# RHD2132-Millmax-RightAngle.net
KiCad netlist of a schematic drawn in EAGLE
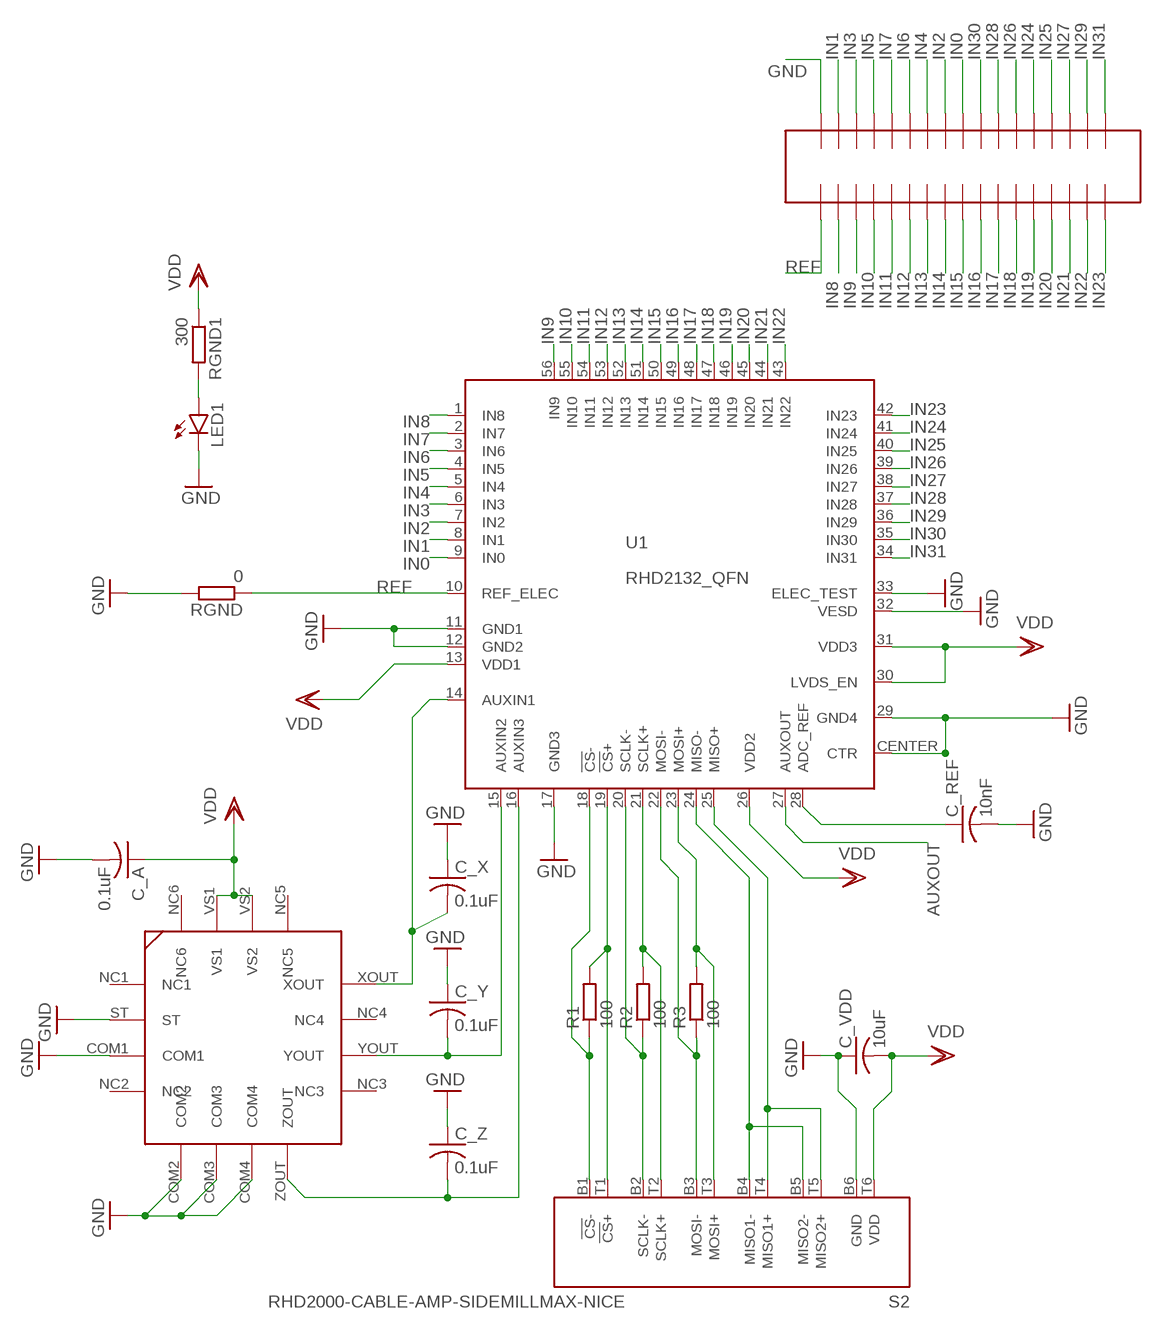
[diagram p0: schematic, sheet 1]

(export (version "E")
  (design (tool "Eeschema 10.0.6"))
  (components
    (comp (ref "C_A")
      (value "0.1uF")
      (footprint "eagle-import:C0402K")
      (libsource (lib "eagle-import") (part "C-USC0402K"))
    )
    (comp (ref "C_REF")
      (value "10nF")
      (footprint "eagle-import:C0402K")
      (libsource (lib "eagle-import") (part "C-USC0402K"))
    )
    (comp (ref "C_VDD")
      (value "10uF")
      (footprint "eagle-import:C1206")
      (libsource (lib "eagle-import") (part "C-USC1206"))
    )
    (comp (ref "C_X")
      (value "0.1uF")
      (footprint "eagle-import:C0402K")
      (libsource (lib "eagle-import") (part "C-USC0402K"))
    )
    (comp (ref "C_Y")
      (value "0.1uF")
      (footprint "eagle-import:C0402K")
      (libsource (lib "eagle-import") (part "C-USC0402K"))
    )
    (comp (ref "C_Z")
      (value "0.1uF")
      (footprint "eagle-import:C0402K")
      (libsource (lib "eagle-import") (part "C-USC0402K"))
    )
    (comp (ref "LED1")
      (value "LEDCHIPLED_0805")
      (footprint "eagle-import:CHIPLED_0805")
      (libsource (lib "eagle-import") (part "LEDCHIPLED_0805"))
    )
    (comp (ref "R1")
      (value "100")
      (footprint "eagle-import:R0402")
      (libsource (lib "eagle-import") (part "R-EU_R0402"))
    )
    (comp (ref "R2")
      (value "100")
      (footprint "eagle-import:R0402")
      (libsource (lib "eagle-import") (part "R-EU_R0402"))
    )
    (comp (ref "R3")
      (value "100")
      (footprint "eagle-import:R0402")
      (libsource (lib "eagle-import") (part "R-EU_R0402"))
    )
    (comp (ref "RGND")
      (value "0")
      (footprint "eagle-import:R0402")
      (libsource (lib "eagle-import") (part "R-EU_R0402"))
    )
    (comp (ref "RGND1")
      (value "300")
      (footprint "eagle-import:R0402")
      (libsource (lib "eagle-import") (part "R-EU_R0402"))
    )
    (comp (ref "S2")
      (value "RHD2000-CABLE-AMP-SIDEMILLMAX-NICE")
      (footprint "eagle-import:MILLMAX-12PIN-NICE")
      (libsource (lib "eagle-import") (part "RHD2000-CABLE-AMP-SIDEMILLMAX-NICE"))
    )
    (comp (ref "U$1")
      (value "ADXL335")
      (footprint "eagle-import:ADXL335")
      (libsource (lib "eagle-import") (part "ADXL335"))
    )
    (comp (ref "U$2")
      (value "FTSH-117BOARD-END")
      (footprint "eagle-import:FTSH-117-END")
      (libsource (lib "eagle-import") (part "FTSH-117BOARD-END"))
    )
    (comp (ref "U1")
      (value "RHD2132_QFN")
      (footprint "eagle-import:QFN56_8_X_8_LARGE")
      (libsource (lib "eagle-import") (part "RHD2132_QFN"))
    )
  )
  (nets
    (net (code "1") (name "/AUXOUT") (class "Default")
      (node (ref "U1") (pin "27") (pinfunction "AUXOUT_27") (pintype "tri_state"))
    )
    (net (code "2") (name "/IN0") (class "Default")
      (node (ref "U$2") (pin "P$26") (pinfunction "P$26_P$26") (pintype "bidirectional"))
      (node (ref "U1") (pin "9") (pinfunction "IN0_9") (pintype "input"))
    )
    (net (code "3") (name "/IN1") (class "Default")
      (node (ref "U$2") (pin "P$33") (pinfunction "P$33_P$33") (pintype "bidirectional"))
      (node (ref "U1") (pin "8") (pinfunction "IN1_8") (pintype "input"))
    )
    (net (code "4") (name "/IN2") (class "Default")
      (node (ref "U$2") (pin "P$27") (pinfunction "P$27_P$27") (pintype "bidirectional"))
      (node (ref "U1") (pin "7") (pinfunction "IN2_7") (pintype "input"))
    )
    (net (code "5") (name "/IN3") (class "Default")
      (node (ref "U$2") (pin "P$32") (pinfunction "P$32_P$32") (pintype "bidirectional"))
      (node (ref "U1") (pin "6") (pinfunction "IN3_6") (pintype "input"))
    )
    (net (code "6") (name "/IN4") (class "Default")
      (node (ref "U$2") (pin "P$28") (pinfunction "P$28_P$28") (pintype "bidirectional"))
      (node (ref "U1") (pin "5") (pinfunction "IN4_5") (pintype "input"))
    )
    (net (code "7") (name "/IN5") (class "Default")
      (node (ref "U$2") (pin "P$31") (pinfunction "P$31_P$31") (pintype "bidirectional"))
      (node (ref "U1") (pin "4") (pinfunction "IN5_4") (pintype "input"))
    )
    (net (code "8") (name "/IN6") (class "Default")
      (node (ref "U$2") (pin "P$29") (pinfunction "P$29_P$29") (pintype "bidirectional"))
      (node (ref "U1") (pin "3") (pinfunction "IN6_3") (pintype "input"))
    )
    (net (code "9") (name "/IN7") (class "Default")
      (node (ref "U$2") (pin "P$30") (pinfunction "P$30_P$30") (pintype "bidirectional"))
      (node (ref "U1") (pin "2") (pinfunction "IN7_2") (pintype "input"))
    )
    (net (code "10") (name "/IN8") (class "Default")
      (node (ref "U$2") (pin "P$2") (pinfunction "P$2_P$2") (pintype "bidirectional"))
      (node (ref "U1") (pin "1") (pinfunction "IN8_1") (pintype "input"))
    )
    (net (code "11") (name "/IN9") (class "Default")
      (node (ref "U$2") (pin "P$3") (pinfunction "P$3_P$3") (pintype "bidirectional"))
      (node (ref "U1") (pin "56") (pinfunction "IN9_56") (pintype "input"))
    )
    (net (code "12") (name "/IN10") (class "Default")
      (node (ref "U$2") (pin "P$4") (pinfunction "P$4_P$4") (pintype "bidirectional"))
      (node (ref "U1") (pin "55") (pinfunction "IN10_55") (pintype "input"))
    )
    (net (code "13") (name "/IN11") (class "Default")
      (node (ref "U$2") (pin "P$5") (pinfunction "P$5_P$5") (pintype "bidirectional"))
      (node (ref "U1") (pin "54") (pinfunction "IN11_54") (pintype "input"))
    )
    (net (code "14") (name "/IN12") (class "Default")
      (node (ref "U$2") (pin "P$6") (pinfunction "P$6_P$6") (pintype "bidirectional"))
      (node (ref "U1") (pin "53") (pinfunction "IN12_53") (pintype "input"))
    )
    (net (code "15") (name "/IN13") (class "Default")
      (node (ref "U$2") (pin "P$7") (pinfunction "P$7_P$7") (pintype "bidirectional"))
      (node (ref "U1") (pin "52") (pinfunction "IN13_52") (pintype "input"))
    )
    (net (code "16") (name "/IN14") (class "Default")
      (node (ref "U$2") (pin "P$8") (pinfunction "P$8_P$8") (pintype "bidirectional"))
      (node (ref "U1") (pin "51") (pinfunction "IN14_51") (pintype "input"))
    )
    (net (code "17") (name "/IN15") (class "Default")
      (node (ref "U$2") (pin "P$9") (pinfunction "P$9_P$9") (pintype "bidirectional"))
      (node (ref "U1") (pin "50") (pinfunction "IN15_50") (pintype "input"))
    )
    (net (code "18") (name "/IN16") (class "Default")
      (node (ref "U$2") (pin "P$10") (pinfunction "P$10_P$10") (pintype "bidirectional"))
      (node (ref "U1") (pin "49") (pinfunction "IN16_49") (pintype "input"))
    )
    (net (code "19") (name "/IN17") (class "Default")
      (node (ref "U$2") (pin "P$11") (pinfunction "P$11_P$11") (pintype "bidirectional"))
      (node (ref "U1") (pin "48") (pinfunction "IN17_48") (pintype "input"))
    )
    (net (code "20") (name "/IN18") (class "Default")
      (node (ref "U$2") (pin "P$12") (pinfunction "P$12_P$12") (pintype "bidirectional"))
      (node (ref "U1") (pin "47") (pinfunction "IN18_47") (pintype "input"))
    )
    (net (code "21") (name "/IN19") (class "Default")
      (node (ref "U$2") (pin "P$13") (pinfunction "P$13_P$13") (pintype "bidirectional"))
      (node (ref "U1") (pin "46") (pinfunction "IN19_46") (pintype "input"))
    )
    (net (code "22") (name "/IN20") (class "Default")
      (node (ref "U$2") (pin "P$14") (pinfunction "P$14_P$14") (pintype "bidirectional"))
      (node (ref "U1") (pin "45") (pinfunction "IN20_45") (pintype "input"))
    )
    (net (code "23") (name "/IN21") (class "Default")
      (node (ref "U$2") (pin "P$15") (pinfunction "P$15_P$15") (pintype "bidirectional"))
      (node (ref "U1") (pin "44") (pinfunction "IN21_44") (pintype "input"))
    )
    (net (code "24") (name "/IN22") (class "Default")
      (node (ref "U$2") (pin "P$16") (pinfunction "P$16_P$16") (pintype "bidirectional"))
      (node (ref "U1") (pin "43") (pinfunction "IN22_43") (pintype "input"))
    )
    (net (code "25") (name "/IN23") (class "Default")
      (node (ref "U$2") (pin "P$17") (pinfunction "P$17_P$17") (pintype "bidirectional"))
      (node (ref "U1") (pin "42") (pinfunction "IN23_42") (pintype "input"))
    )
    (net (code "26") (name "/IN24") (class "Default")
      (node (ref "U$2") (pin "P$22") (pinfunction "P$22_P$22") (pintype "bidirectional"))
      (node (ref "U1") (pin "41") (pinfunction "IN24_41") (pintype "input"))
    )
    (net (code "27") (name "/IN25") (class "Default")
      (node (ref "U$2") (pin "P$21") (pinfunction "P$21_P$21") (pintype "bidirectional"))
      (node (ref "U1") (pin "40") (pinfunction "IN25_40") (pintype "input"))
    )
    (net (code "28") (name "/IN26") (class "Default")
      (node (ref "U$2") (pin "P$23") (pinfunction "P$23_P$23") (pintype "bidirectional"))
      (node (ref "U1") (pin "39") (pinfunction "IN26_39") (pintype "input"))
    )
    (net (code "29") (name "/IN27") (class "Default")
      (node (ref "U$2") (pin "P$20") (pinfunction "P$20_P$20") (pintype "bidirectional"))
      (node (ref "U1") (pin "38") (pinfunction "IN27_38") (pintype "input"))
    )
    (net (code "30") (name "/IN28") (class "Default")
      (node (ref "U$2") (pin "P$24") (pinfunction "P$24_P$24") (pintype "bidirectional"))
      (node (ref "U1") (pin "37") (pinfunction "IN28_37") (pintype "input"))
    )
    (net (code "31") (name "/IN29") (class "Default")
      (node (ref "U$2") (pin "P$19") (pinfunction "P$19_P$19") (pintype "bidirectional"))
      (node (ref "U1") (pin "36") (pinfunction "IN29_36") (pintype "input"))
    )
    (net (code "32") (name "/IN30") (class "Default")
      (node (ref "U$2") (pin "P$25") (pinfunction "P$25_P$25") (pintype "bidirectional"))
      (node (ref "U1") (pin "35") (pinfunction "IN30_35") (pintype "input"))
    )
    (net (code "33") (name "/IN31") (class "Default")
      (node (ref "U$2") (pin "P$18") (pinfunction "P$18_P$18") (pintype "bidirectional"))
      (node (ref "U1") (pin "34") (pinfunction "IN31_34") (pintype "input"))
    )
    (net (code "34") (name "/REF") (class "Default")
      (node (ref "RGND") (pin "1") (pinfunction "1_1") (pintype "passive"))
      (node (ref "U$2") (pin "P$1") (pinfunction "P$1_P$1") (pintype "bidirectional"))
      (node (ref "U1") (pin "10") (pinfunction "REF_ELEC_10") (pintype "input"))
    )
    (net (code "35") (name "GND") (class "Default")
      (node (ref "C_A") (pin "2") (pinfunction "2_2") (pintype "passive"))
      (node (ref "C_REF") (pin "2") (pinfunction "2_2") (pintype "passive"))
      (node (ref "C_VDD") (pin "1") (pinfunction "1_1") (pintype "passive"))
      (node (ref "C_X") (pin "1") (pinfunction "1_1") (pintype "passive"))
      (node (ref "C_Y") (pin "1") (pinfunction "1_1") (pintype "passive"))
      (node (ref "C_Z") (pin "1") (pinfunction "1_1") (pintype "passive"))
      (node (ref "LED1") (pin "C") (pinfunction "C_C") (pintype "passive"))
      (node (ref "RGND") (pin "2") (pinfunction "2_2") (pintype "passive"))
      (node (ref "S2") (pin "B6") (pinfunction "GND_B6") (pintype "power_in"))
      (node (ref "U$1") (pin "COM1") (pinfunction "COM1_COM1") (pintype "bidirectional"))
      (node (ref "U$1") (pin "COM2") (pinfunction "COM2_COM2") (pintype "bidirectional"))
      (node (ref "U$1") (pin "COM3") (pinfunction "COM3_COM3") (pintype "bidirectional"))
      (node (ref "U$1") (pin "COM4") (pinfunction "COM4_COM4") (pintype "bidirectional"))
      (node (ref "U$1") (pin "ST") (pinfunction "ST_ST") (pintype "bidirectional"))
      (node (ref "U$2") (pin "P$34") (pinfunction "P$34_P$34") (pintype "bidirectional"))
      (node (ref "U1") (pin "11") (pinfunction "GND1_11") (pintype "power_in"))
      (node (ref "U1") (pin "12") (pinfunction "GND2_12") (pintype "power_in"))
      (node (ref "U1") (pin "17") (pinfunction "GND3_17") (pintype "power_in"))
      (node (ref "U1") (pin "29") (pinfunction "GND4_29") (pintype "power_in"))
      (node (ref "U1") (pin "32") (pinfunction "VESD_32") (pintype "power_in"))
      (node (ref "U1") (pin "33") (pinfunction "ELEC_TEST_33") (pintype "input"))
      (node (ref "U1") (pin "CENTER") (pinfunction "CTR_CENTER") (pintype "power_in"))
    )
    (net (code "36") (name "Net-(LED1-PadA)") (class "Default")
      (node (ref "LED1") (pin "A") (pinfunction "A_A") (pintype "passive"))
      (node (ref "RGND1") (pin "2") (pinfunction "2_2") (pintype "passive"))
    )
    (net (code "37") (name "Net-(S2-MISO1+)") (class "Default")
      (node (ref "S2") (pin "T4") (pinfunction "MISO1+_T4") (pintype "bidirectional"))
      (node (ref "S2") (pin "T5") (pinfunction "MISO2+_T5") (pintype "bidirectional"))
      (node (ref "U1") (pin "25") (pinfunction "MISO+_25") (pintype "output"))
    )
    (net (code "38") (name "Net-(S2-MISO1-)") (class "Default")
      (node (ref "S2") (pin "B4") (pinfunction "MISO1-_B4") (pintype "bidirectional"))
      (node (ref "S2") (pin "B5") (pinfunction "MISO2-_B5") (pintype "bidirectional"))
      (node (ref "U1") (pin "24") (pinfunction "MISO-_24") (pintype "output"))
    )
    (net (code "39") (name "Net-(S2-MOSI+)") (class "Default")
      (node (ref "R3") (pin "2") (pinfunction "2_2") (pintype "passive"))
      (node (ref "S2") (pin "T3") (pinfunction "MOSI+_T3") (pintype "bidirectional"))
      (node (ref "U1") (pin "23") (pinfunction "MOSI+_23") (pintype "input"))
    )
    (net (code "40") (name "Net-(S2-MOSI-)") (class "Default")
      (node (ref "R3") (pin "1") (pinfunction "1_1") (pintype "passive"))
      (node (ref "S2") (pin "B3") (pinfunction "MOSI-_B3") (pintype "bidirectional"))
      (node (ref "U1") (pin "22") (pinfunction "MOSI-_22") (pintype "input"))
    )
    (net (code "41") (name "Net-(S2-SCLK+)") (class "Default")
      (node (ref "R2") (pin "2") (pinfunction "2_2") (pintype "passive"))
      (node (ref "S2") (pin "T2") (pinfunction "SCLK+_T2") (pintype "bidirectional"))
      (node (ref "U1") (pin "21") (pinfunction "SCLK+_21") (pintype "input"))
    )
    (net (code "42") (name "Net-(S2-SCLK-)") (class "Default")
      (node (ref "R2") (pin "1") (pinfunction "1_1") (pintype "passive"))
      (node (ref "S2") (pin "B2") (pinfunction "SCLK-_B2") (pintype "bidirectional"))
      (node (ref "U1") (pin "20") (pinfunction "SCLK-_20") (pintype "input"))
    )
    (net (code "43") (name "Net-(S2-~{CS}+)") (class "Default")
      (node (ref "R1") (pin "2") (pinfunction "2_2") (pintype "passive"))
      (node (ref "S2") (pin "T1") (pinfunction "~{CS}+_T1") (pintype "bidirectional"))
      (node (ref "U1") (pin "19") (pinfunction "~{CS}+_19") (pintype "input"))
    )
    (net (code "44") (name "Net-(S2-~{CS}-)") (class "Default")
      (node (ref "R1") (pin "1") (pinfunction "1_1") (pintype "passive"))
      (node (ref "S2") (pin "B1") (pinfunction "~{CS}-_B1") (pintype "bidirectional"))
      (node (ref "U1") (pin "18") (pinfunction "~{CS}-_18") (pintype "input"))
    )
    (net (code "45") (name "Net-(U1-ADC_REF)") (class "Default")
      (node (ref "C_REF") (pin "1") (pinfunction "1_1") (pintype "passive"))
      (node (ref "U1") (pin "28") (pinfunction "ADC_REF_28") (pintype "passive"))
    )
    (net (code "46") (name "Net-(U1-AUXIN1)") (class "Default")
      (node (ref "C_X") (pin "2") (pinfunction "2_2") (pintype "passive"))
      (node (ref "U$1") (pin "XOUT") (pinfunction "XOUT_XOUT") (pintype "bidirectional"))
      (node (ref "U1") (pin "14") (pinfunction "AUXIN1_14") (pintype "input"))
    )
    (net (code "47") (name "Net-(U1-AUXIN2)") (class "Default")
      (node (ref "C_Y") (pin "2") (pinfunction "2_2") (pintype "passive"))
      (node (ref "U$1") (pin "YOUT") (pinfunction "YOUT_YOUT") (pintype "bidirectional"))
      (node (ref "U1") (pin "15") (pinfunction "AUXIN2_15") (pintype "input"))
    )
    (net (code "48") (name "Net-(U1-AUXIN3)") (class "Default")
      (node (ref "C_Z") (pin "2") (pinfunction "2_2") (pintype "passive"))
      (node (ref "U$1") (pin "ZOUT") (pinfunction "ZOUT_ZOUT") (pintype "bidirectional"))
      (node (ref "U1") (pin "16") (pinfunction "AUXIN3_16") (pintype "input"))
    )
    (net (code "49") (name "VDD") (class "Default")
      (node (ref "C_A") (pin "1") (pinfunction "1_1") (pintype "passive"))
      (node (ref "C_VDD") (pin "2") (pinfunction "2_2") (pintype "passive"))
      (node (ref "RGND1") (pin "1") (pinfunction "1_1") (pintype "passive"))
      (node (ref "S2") (pin "T6") (pinfunction "VDD_T6") (pintype "bidirectional"))
      (node (ref "U$1") (pin "VS1") (pinfunction "VS1_VS1") (pintype "bidirectional"))
      (node (ref "U$1") (pin "VS2") (pinfunction "VS2_VS2") (pintype "bidirectional"))
      (node (ref "U1") (pin "13") (pinfunction "VDD1_13") (pintype "power_in"))
      (node (ref "U1") (pin "26") (pinfunction "VDD2_26") (pintype "power_in"))
      (node (ref "U1") (pin "30") (pinfunction "LVDS_EN_30") (pintype "input"))
      (node (ref "U1") (pin "31") (pinfunction "VDD3_31") (pintype "power_in"))
    )
    (net (code "50") (name "unconnected-(U$1-PadNC1)") (class "Default")
      (node (ref "U$1") (pin "NC1") (pinfunction "NC1_NC1") (pintype "bidirectional"))
    )
    (net (code "51") (name "unconnected-(U$1-PadNC2)") (class "Default")
      (node (ref "U$1") (pin "NC2") (pinfunction "NC2_NC2") (pintype "bidirectional"))
    )
    (net (code "52") (name "unconnected-(U$1-PadNC3)") (class "Default")
      (node (ref "U$1") (pin "NC3") (pinfunction "NC3_NC3") (pintype "bidirectional"))
    )
    (net (code "53") (name "unconnected-(U$1-PadNC4)") (class "Default")
      (node (ref "U$1") (pin "NC4") (pinfunction "NC4_NC4") (pintype "bidirectional"))
    )
    (net (code "54") (name "unconnected-(U$1-PadNC5)") (class "Default")
      (node (ref "U$1") (pin "NC5") (pinfunction "NC5_NC5") (pintype "bidirectional"))
    )
    (net (code "55") (name "unconnected-(U$1-PadNC6)") (class "Default")
      (node (ref "U$1") (pin "NC6") (pinfunction "NC6_NC6") (pintype "bidirectional"))
    )
  )
)
